# can_tcan1462v.net
KiCad netlist of a schematic drawn in Altium Designer
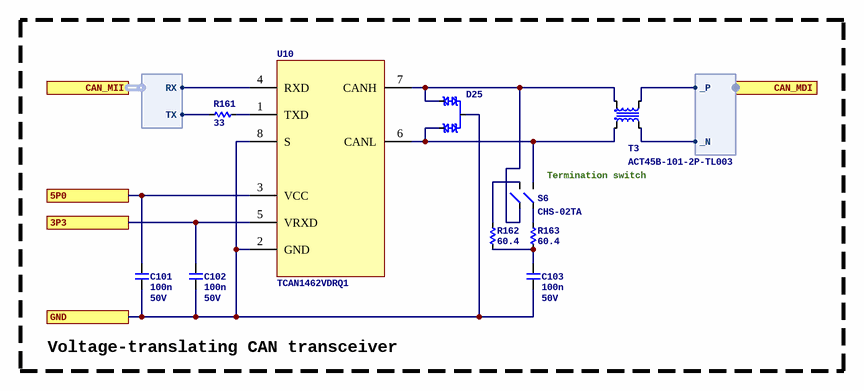
[diagram p0: can_tcan1462v.SchDoc]

(export (version "E")
  (design (tool "Eeschema 10.0.6"))
  (components
    (comp (ref "C101")
      (value "CL05B104KB54PNC")
      (footprint "C0402")
      (fields
        (field (name "CAPACITANCE") "100n")
        (field (name "MANUFACTURER") "Samsung Electro-Mechanics")
        (field (name "VOLTAGE RATING") "50V")
      )
      (libsource (lib "database") (part "__template_cap"))
    )
    (comp (ref "C102")
      (value "CL05B104KB54PNC")
      (footprint "C0402")
      (fields
        (field (name "CAPACITANCE") "100n")
        (field (name "MANUFACTURER") "Samsung Electro-Mechanics")
        (field (name "VOLTAGE RATING") "50V")
      )
      (libsource (lib "database") (part "__template_cap"))
    )
    (comp (ref "C103")
      (value "CL05B104KB54PNC")
      (footprint "C0402")
      (fields
        (field (name "CAPACITANCE") "100n")
        (field (name "MANUFACTURER") "Samsung Electro-Mechanics")
        (field (name "VOLTAGE RATING") "50V")
      )
      (libsource (lib "database") (part "__template_cap"))
    )
    (comp (ref "D25")
      (value "PESD2CAN,215")
      (footprint "3SOT23")
      (description "DIODE ESD CAN SOT-23")
      (fields (field (name "MANUFACTURER") "NXP Semiconductors"))
      (libsource (lib "SSCP") (part "TVS_PESD2CAN"))
    )
    (comp (ref "R161")
      (value "33")
      (footprint "R0402")
      (fields
        (field (name "TOLERANCE") "1%")
        (field (name "MANUFACTURER PART NUMBER") "0402WGF330JTCE")
        (field (name "MANUFACTURER") "UNI-ROYAL(Uniroyal Elec)")
      )
      (libsource (lib "database") (part "__template_resistor"))
    )
    (comp (ref "R162")
      (value "60.4")
      (footprint "R0402")
      (fields
        (field (name "TOLERANCE") "1%")
        (field (name "MANUFACTURER PART NUMBER") "FRC0402F60R4TS")
        (field (name "MANUFACTURER") "FOJAN")
      )
      (libsource (lib "database") (part "__template_resistor"))
    )
    (comp (ref "R163")
      (value "60.4")
      (footprint "R0402")
      (fields
        (field (name "TOLERANCE") "1%")
        (field (name "MANUFACTURER PART NUMBER") "FRC0402F60R4TS")
        (field (name "MANUFACTURER") "FOJAN")
      )
      (libsource (lib "database") (part "__template_resistor"))
    )
    (comp (ref "S6")
      (value "CHS-02TA")
      (footprint "SWITCH_NIDEC_CHS-02TA")
      (description "DIP Switch, Slide, SPST, Flush, Recessed, 6VDC, 100mA, CHS Series ¦ Nidec Components CHS-02TA")
      (fields (field (name "MANUFACTURER") "Nidec Copal"))
      (libsource (lib "SSCP") (part "SWITCH_CHS-02TA"))
    )
    (comp (ref "T3")
      (value "CHOKE_ACT45B-101-2P-TL003")
      (footprint "CHOKE_ACT45B-101-2P-TL003")
      (description "CHOKE COMMON MODE 5000 OHM SMD")
      (fields
        (field (name "MANUFACTURER") "TDK Corporation")
        (field (name "MANUFACTURER PART NUMBER") "ACT45B-101-2P-TL003")
      )
      (libsource (lib "SSCP") (part "CHOKE_ACT45B-101-2P-TL003"))
    )
    (comp (ref "U10")
      (value "TCAN1462VDRQ1")
      (footprint "8SOIC150")
      (description "Automotive signal improvement CAN FD transceiver with VIO and standby 8-SOIC -40 to 125")
      (fields (field (name "MANUFACTURER") "Texas Instruments"))
      (libsource (lib "SSCP") (part "CAN_TCAN1462VDRQ1"))
    )
  )
  (nets
    (net (code "3") (name "/3P3") (class "Default")
      (node (ref "C102") (pin "1") (pintype "passive"))
      (node (ref "U10") (pin "5") (pinfunction "VRXD_5") (pintype "passive"))
    )
    (net (code "4") (name "/5P0") (class "Default")
      (node (ref "C101") (pin "1") (pintype "passive"))
      (node (ref "U10") (pin "3") (pinfunction "VCC_3") (pintype "passive"))
    )
    (net (code "5") (name "/GND") (class "Default")
      (node (ref "C101") (pin "2") (pintype "passive"))
      (node (ref "C102") (pin "2") (pintype "passive"))
      (node (ref "C103") (pin "2") (pintype "passive"))
      (node (ref "D25") (pin "3") (pintype "passive"))
      (node (ref "U10") (pin "2") (pinfunction "GND_2") (pintype "passive"))
      (node (ref "U10") (pin "8") (pinfunction "S_8") (pintype "passive"))
    )
    (net (code "6") (name "/RX") (class "Default")
      (node (ref "U10") (pin "4") (pinfunction "RXD_4") (pintype "passive"))
    )
    (net (code "7") (name "/TX") (class "Default") (node (ref "R161") (pin "1") (pintype "passive")))
    (net (code "8") (name "/_N") (class "Default") (node (ref "T3") (pin "4") (pintype "passive")))
    (net (code "9") (name "/_P") (class "Default") (node (ref "T3") (pin "3") (pintype "passive")))
    (net (code "12") (name "Net-(C103-Pad1)") (class "Default")
      (node (ref "C103") (pin "1") (pintype "passive"))
      (node (ref "R162") (pin "2") (pintype "passive"))
      (node (ref "R163") (pin "1") (pintype "passive"))
    )
    (net (code "13") (name "Net-(R162-Pad1)") (class "Default")
      (node (ref "R162") (pin "1") (pintype "passive"))
      (node (ref "S6") (pin "2") (pintype "passive"))
    )
    (net (code "14") (name "Net-(R163-Pad2)") (class "Default")
      (node (ref "R163") (pin "2") (pintype "passive"))
      (node (ref "S6") (pin "3") (pintype "passive"))
    )
    (net (code "15") (name "Net-(U10-CANH)") (class "Default")
      (node (ref "D25") (pin "1") (pintype "passive"))
      (node (ref "S6") (pin "1") (pintype "passive"))
      (node (ref "T3") (pin "2") (pintype "passive"))
      (node (ref "U10") (pin "7") (pinfunction "CANH_7") (pintype "passive"))
    )
    (net (code "16") (name "Net-(U10-CANL)") (class "Default")
      (node (ref "D25") (pin "2") (pintype "passive"))
      (node (ref "S6") (pin "4") (pintype "passive"))
      (node (ref "T3") (pin "1") (pintype "passive"))
      (node (ref "U10") (pin "6") (pinfunction "CANL_6") (pintype "passive"))
    )
    (net (code "17") (name "Net-(U10-TXD)") (class "Default")
      (node (ref "R161") (pin "2") (pintype "passive"))
      (node (ref "U10") (pin "1") (pinfunction "TXD_1") (pintype "passive"))
    )
  )
)
